# button_panel.net
KiCad netlist of a schematic drawn in Altium Designer
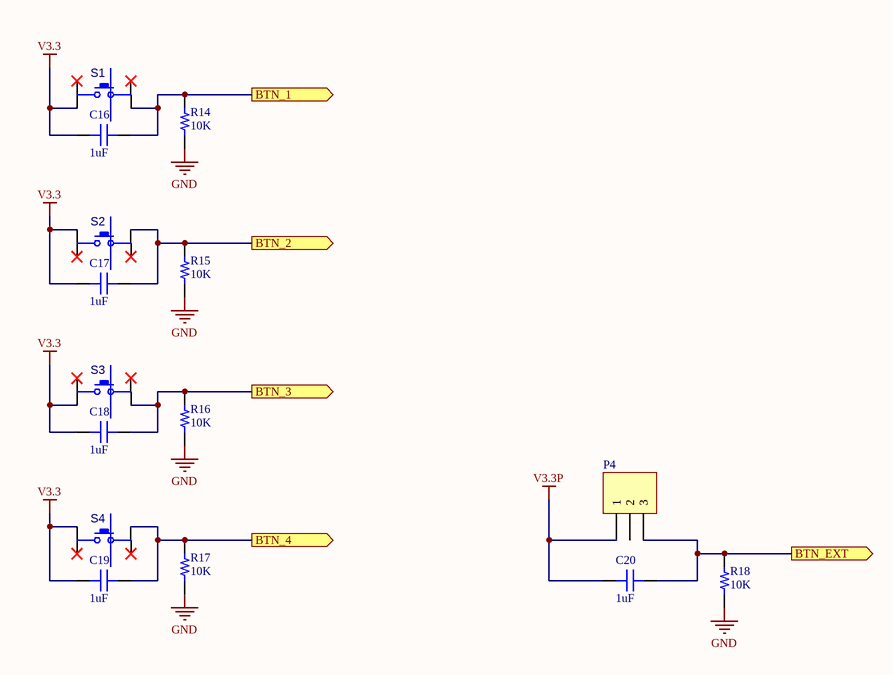
[diagram p0: button_panel.SchDoc]

(export (version "E")
  (design (tool "Eeschema 10.0.6"))
  (components
    (comp (ref "C16")
      (value "1uF")
      (footprint "CAP 0603_1608")
      (description "SMT Capacitor")
      (fields (field (name "MF") "Murata") (field (name "MP") "GRT188R61H105KE13D"))
      (libsource (lib "Capacitor") (part "Capacitor"))
    )
    (comp (ref "C17")
      (value "1uF")
      (footprint "CAP 0603_1608")
      (description "SMT Capacitor")
      (fields (field (name "MF") "Murata") (field (name "MP") "GRT188R61H105KE13D"))
      (libsource (lib "Capacitor") (part "Capacitor"))
    )
    (comp (ref "C18")
      (value "1uF")
      (footprint "CAP 0603_1608")
      (description "SMT Capacitor")
      (fields (field (name "MF") "Murata") (field (name "MP") "GRT188R61H105KE13D"))
      (libsource (lib "Capacitor") (part "Capacitor"))
    )
    (comp (ref "C19")
      (value "1uF")
      (footprint "CAP 0603_1608")
      (description "SMT Capacitor")
      (fields (field (name "MF") "Murata") (field (name "MP") "GRT188R61H105KE13D"))
      (libsource (lib "Capacitor") (part "Capacitor"))
    )
    (comp (ref "C20")
      (value "1uF")
      (footprint "CAP 0603_1608")
      (description "SMT Capacitor")
      (fields (field (name "MF") "Murata") (field (name "MP") "GRT188R61H105KE13D"))
      (libsource (lib "Capacitor") (part "Capacitor"))
    )
    (comp (ref "P4")
      (value "~")
      (footprint "TEConn_EP2.5_1x3")
      (description "Header, 3-Pin, Right Angle")
      (fields
        (field (name "MF") "TE Connectivity")
        (field (name "MP") "1744426-3")
        (field (name "PUBLISHER") "Altium Limited")
      )
      (libsource (lib "Connector") (part "Header 3H"))
    )
    (comp (ref "R14")
      (value "10K")
      (footprint "RES 0603_1608")
      (description "SMT Resistor")
      (fields (field (name "MF") "YAGEO") (field (name "MP") "AC0603FR-0710KL"))
      (libsource (lib "Resistor") (part "Resistor"))
    )
    (comp (ref "R15")
      (value "10K")
      (footprint "RES 0603_1608")
      (description "SMT Resistor")
      (fields (field (name "MF") "YAGEO") (field (name "MP") "AC0603FR-0710KL"))
      (libsource (lib "Resistor") (part "Resistor"))
    )
    (comp (ref "R16")
      (value "10K")
      (footprint "RES 0603_1608")
      (description "SMT Resistor")
      (fields (field (name "MF") "YAGEO") (field (name "MP") "AC0603FR-0710KL"))
      (libsource (lib "Resistor") (part "Resistor"))
    )
    (comp (ref "R17")
      (value "10K")
      (footprint "RES 0603_1608")
      (description "SMT Resistor")
      (fields (field (name "MF") "YAGEO") (field (name "MP") "AC0603FR-0710KL"))
      (libsource (lib "Resistor") (part "Resistor"))
    )
    (comp (ref "R18")
      (value "10K")
      (footprint "RES 0603_1608")
      (description "SMT Resistor")
      (fields (field (name "MF") "YAGEO") (field (name "MP") "AC0603FR-0710KL"))
      (libsource (lib "Resistor") (part "Resistor"))
    )
    (comp (ref "S1")
      (value "SPST-NO")
      (footprint "C&K PTS125 H7.3")
      (description "SWITCH, PUSH BUTTON, TACTILE, SMD, SPDT, 6X6X7mm")
      (fields (field (name "MF") "C&K") (field (name "MP") "PTS125SJM73SMTR2LFS"))
      (libsource (lib "Switch") (part "SPST-NO 4 PIN ALT1"))
    )
    (comp (ref "S2")
      (value "SPST-NO")
      (footprint "C&K PTS125 H7.3")
      (description "SWITCH, PUSH BUTTON, TACTILE, SMD, SPDT, 6X6X7mm")
      (fields (field (name "MF") "C&K") (field (name "MP") "PTS125SJM73SMTR2LFS"))
      (libsource (lib "Switch") (part "SPST-NO 4 PIN ALT1"))
    )
    (comp (ref "S3")
      (value "SPST-NO")
      (footprint "C&K PTS125 H7.3")
      (description "SWITCH, PUSH BUTTON, TACTILE, SMD, SPDT, 6X6X7mm")
      (fields (field (name "MF") "C&K") (field (name "MP") "PTS125SJM73SMTR2LFS"))
      (libsource (lib "Switch") (part "SPST-NO 4 PIN ALT1"))
    )
    (comp (ref "S4")
      (value "SPST-NO")
      (footprint "C&K PTS125 H7.3")
      (description "SWITCH, PUSH BUTTON, TACTILE, SMD, SPDT, 6X6X7mm")
      (fields (field (name "MF") "C&K") (field (name "MP") "PTS125SJM73SMTR2LFS"))
      (libsource (lib "Switch") (part "SPST-NO 4 PIN ALT1"))
    )
  )
  (nets
    (net (code "1") (name "/BTN_1") (class "Default")
      (node (ref "C16") (pin "1") (pinfunction "1_1") (pintype "passive"))
      (node (ref "R14") (pin "1") (pinfunction "1_1") (pintype "passive"))
      (node (ref "S1") (pin "4") (pinfunction "P2_4") (pintype "passive"))
    )
    (net (code "2") (name "/BTN_2") (class "Default")
      (node (ref "C17") (pin "1") (pinfunction "1_1") (pintype "passive"))
      (node (ref "R15") (pin "1") (pinfunction "1_1") (pintype "passive"))
      (node (ref "S2") (pin "3") (pinfunction "P4_3") (pintype "passive"))
    )
    (net (code "3") (name "/BTN_3") (class "Default")
      (node (ref "C18") (pin "1") (pinfunction "1_1") (pintype "passive"))
      (node (ref "R16") (pin "1") (pinfunction "1_1") (pintype "passive"))
      (node (ref "S3") (pin "4") (pinfunction "P2_4") (pintype "passive"))
    )
    (net (code "4") (name "/BTN_4") (class "Default")
      (node (ref "C19") (pin "1") (pinfunction "1_1") (pintype "passive"))
      (node (ref "R17") (pin "1") (pinfunction "1_1") (pintype "passive"))
      (node (ref "S4") (pin "3") (pinfunction "P4_3") (pintype "passive"))
    )
    (net (code "5") (name "/BTN_EXT") (class "Default")
      (node (ref "C20") (pin "1") (pinfunction "1_1") (pintype "passive"))
      (node (ref "P4") (pin "3") (pinfunction "3_3") (pintype "passive"))
      (node (ref "R18") (pin "1") (pinfunction "1_1") (pintype "passive"))
    )
    (net (code "6") (name "GND") (class "Default")
      (node (ref "R14") (pin "2") (pinfunction "2_2") (pintype "passive"))
      (node (ref "R15") (pin "2") (pinfunction "2_2") (pintype "passive"))
      (node (ref "R16") (pin "2") (pinfunction "2_2") (pintype "passive"))
      (node (ref "R17") (pin "2") (pinfunction "2_2") (pintype "passive"))
      (node (ref "R18") (pin "2") (pinfunction "2_2") (pintype "passive"))
    )
    (net (code "7") (name "V3.3") (class "Default")
      (node (ref "C16") (pin "2") (pinfunction "2_2") (pintype "passive"))
      (node (ref "C17") (pin "2") (pinfunction "2_2") (pintype "passive"))
      (node (ref "C18") (pin "2") (pinfunction "2_2") (pintype "passive"))
      (node (ref "C19") (pin "2") (pinfunction "2_2") (pintype "passive"))
      (node (ref "S1") (pin "2") (pinfunction "P3_2") (pintype "passive"))
      (node (ref "S2") (pin "1") (pinfunction "P1_1") (pintype "passive"))
      (node (ref "S3") (pin "2") (pinfunction "P3_2") (pintype "passive"))
      (node (ref "S4") (pin "1") (pinfunction "P1_1") (pintype "passive"))
    )
    (net (code "8") (name "V3.3P") (class "Default")
      (node (ref "C20") (pin "2") (pinfunction "2_2") (pintype "passive"))
      (node (ref "P4") (pin "1") (pinfunction "1_1") (pintype "passive"))
    )
    (net (code "9") (name "unconnected-(P4-Pad2)") (class "Default")
      (node (ref "P4") (pin "2") (pinfunction "2_2") (pintype "passive"))
    )
    (net (code "10") (name "unconnected-(S1-P1-Pad1)") (class "Default")
      (node (ref "S1") (pin "1") (pinfunction "P1_1") (pintype "passive+no_connect"))
    )
    (net (code "11") (name "unconnected-(S1-P4-Pad3)") (class "Default")
      (node (ref "S1") (pin "3") (pinfunction "P4_3") (pintype "passive+no_connect"))
    )
    (net (code "12") (name "unconnected-(S2-P2-Pad4)") (class "Default")
      (node (ref "S2") (pin "4") (pinfunction "P2_4") (pintype "passive+no_connect"))
    )
    (net (code "13") (name "unconnected-(S2-P3-Pad2)") (class "Default")
      (node (ref "S2") (pin "2") (pinfunction "P3_2") (pintype "passive+no_connect"))
    )
    (net (code "14") (name "unconnected-(S3-P1-Pad1)") (class "Default")
      (node (ref "S3") (pin "1") (pinfunction "P1_1") (pintype "passive+no_connect"))
    )
    (net (code "15") (name "unconnected-(S3-P4-Pad3)") (class "Default")
      (node (ref "S3") (pin "3") (pinfunction "P4_3") (pintype "passive+no_connect"))
    )
    (net (code "16") (name "unconnected-(S4-P2-Pad4)") (class "Default")
      (node (ref "S4") (pin "4") (pinfunction "P2_4") (pintype "passive+no_connect"))
    )
    (net (code "17") (name "unconnected-(S4-P3-Pad2)") (class "Default")
      (node (ref "S4") (pin "2") (pinfunction "P3_2") (pintype "passive+no_connect"))
    )
  )
)
